# VCA.net
KiCad netlist of a schematic drawn in EAGLE
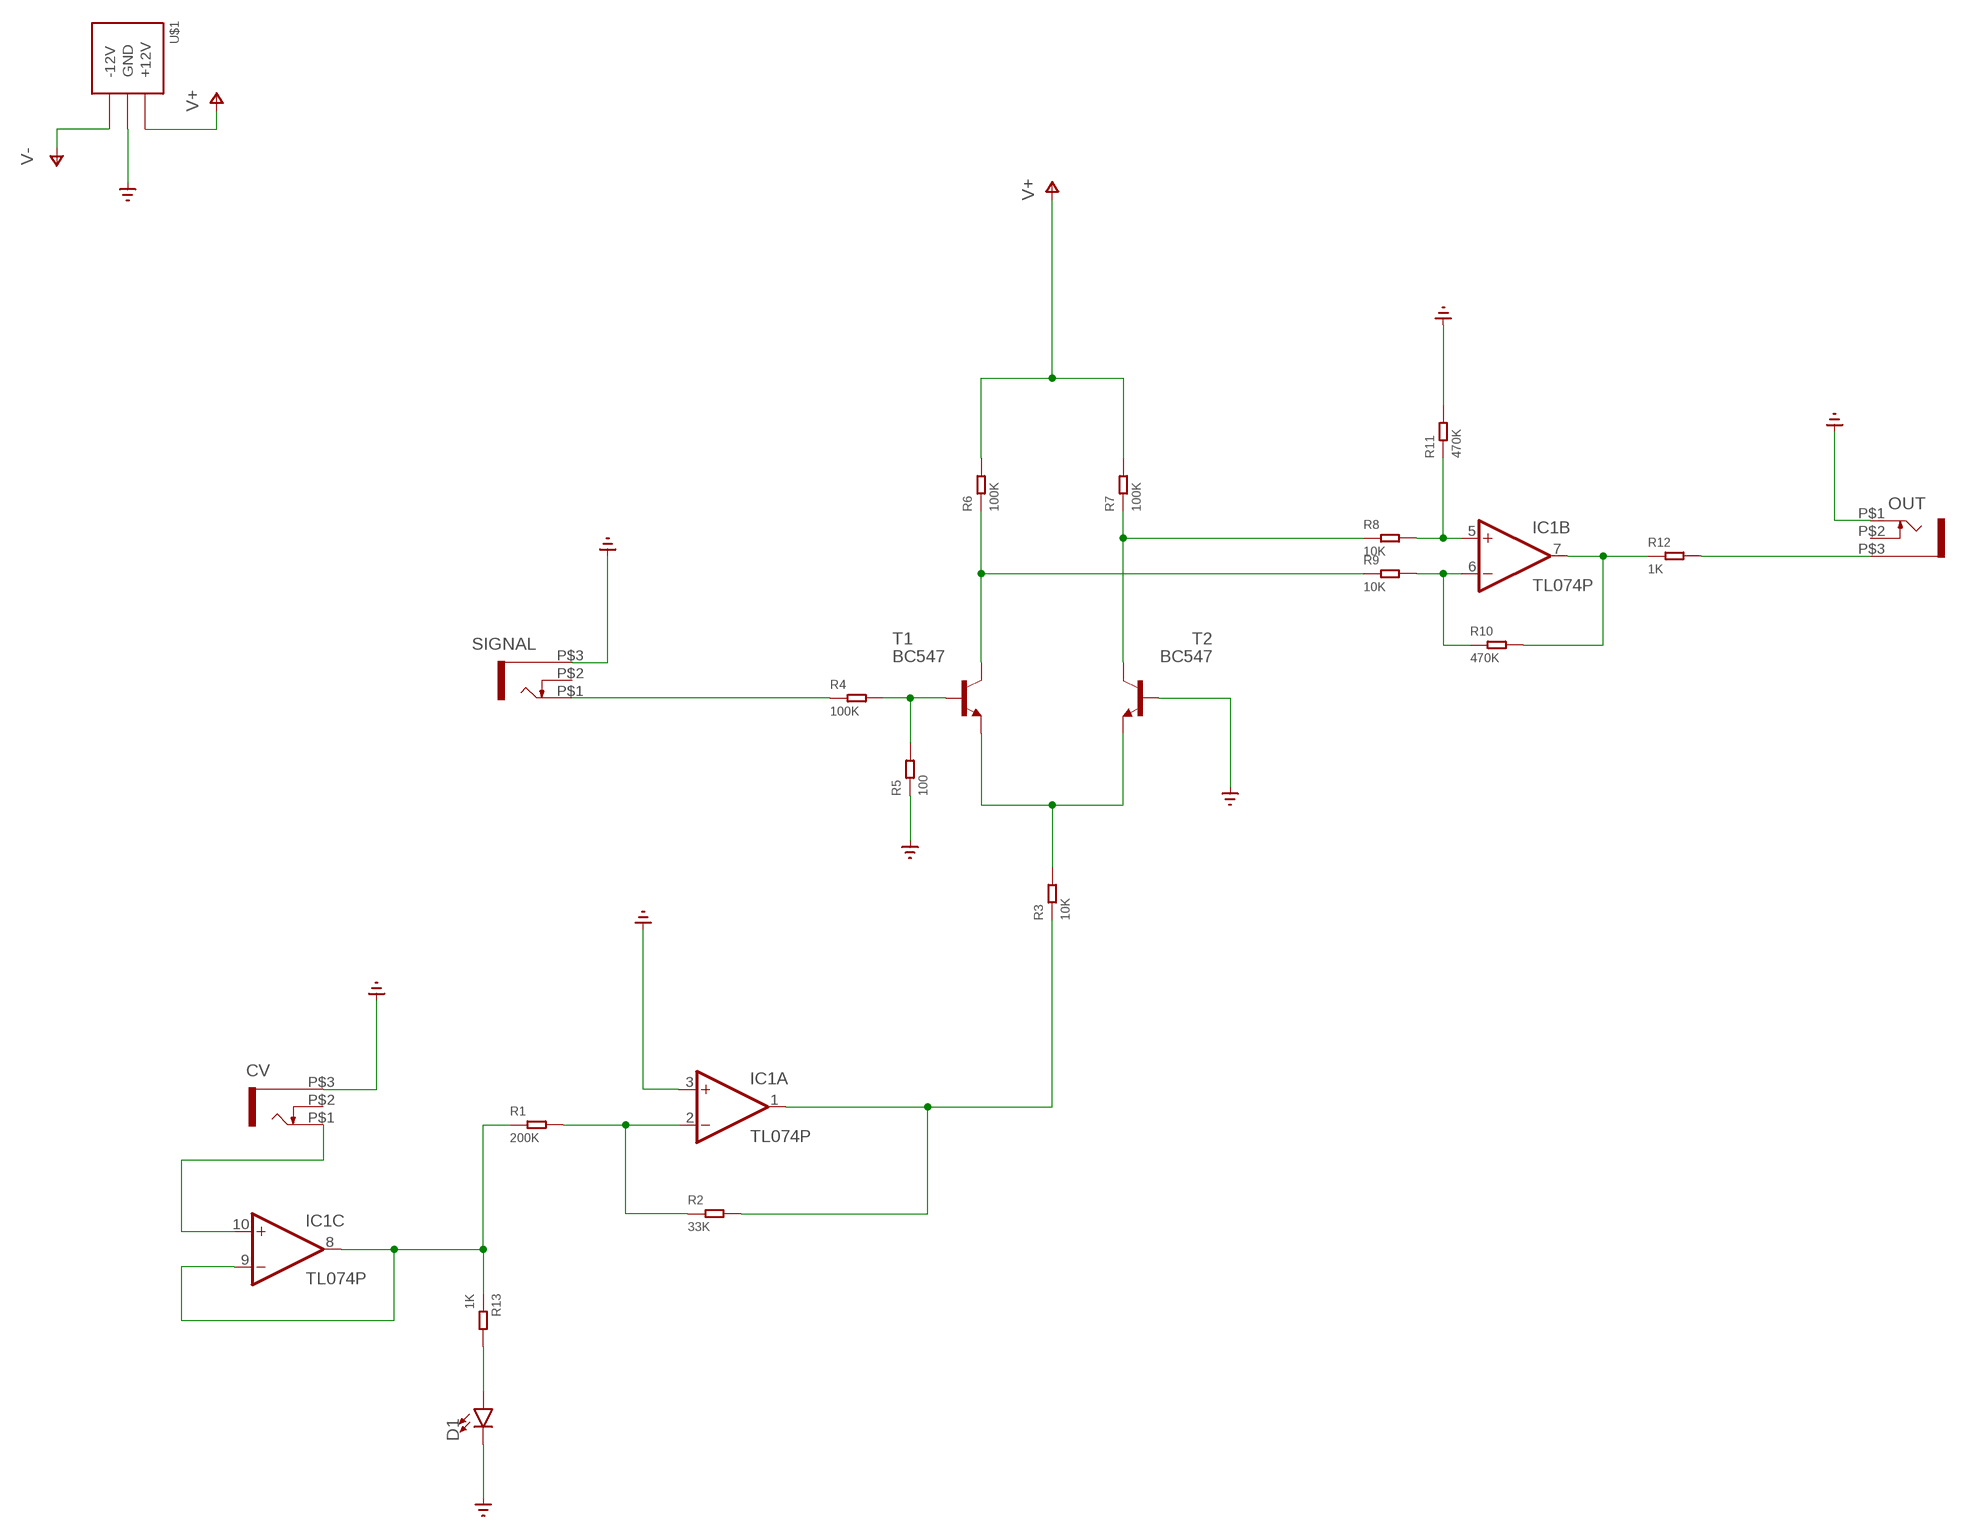
[diagram p0: schematic, sheet 1]

(export (version "E")
  (design (tool "Eeschema 10.0.6"))
  (components
    (comp (ref "CV")
      (value "WQP-PJ301M-12_JACK")
      (footprint "eagle-import:WQP-PJ301M-12_JACK")
      (libsource (lib "eagle-import") (part "WQP-PJ301M-12_JACK"))
    )
    (comp (ref "D1")
      (value "LED3MM")
      (footprint "eagle-import:LED_3MM")
      (libsource (lib "eagle-import") (part "LED3MM"))
    )
    (comp (ref "IC1")
      (value "TL074P")
      (footprint "eagle-import:DIL14")
      (libsource (lib "eagle-import") (part "TL074P"))
    )
    (comp (ref "OUT")
      (value "WQP-PJ301M-12_JACK")
      (footprint "eagle-import:WQP-PJ301M-12_JACK")
      (libsource (lib "eagle-import") (part "WQP-PJ301M-12_JACK"))
    )
    (comp (ref "R1")
      (value "200K")
      (footprint "eagle-import:PR-D2.3XL6.5MM")
      (fields (field (name "MPN") "FHCFR-1/4W-102J"))
      (libsource (lib "eagle-import") (part "DIP-RES-1K-5%-1/4W(PR-D2.3XL6.5MM)"))
    )
    (comp (ref "R2")
      (value "33K")
      (footprint "eagle-import:PR-D2.3XL6.5MM")
      (fields (field (name "MPN") "FHCFR-1/4W-102J"))
      (libsource (lib "eagle-import") (part "DIP-RES-1K-5%-1/4W(PR-D2.3XL6.5MM)"))
    )
    (comp (ref "R3")
      (value "10K")
      (footprint "eagle-import:PR-D2.3XL6.5MM")
      (fields (field (name "MPN") "FHCFR-1/4W-102J"))
      (libsource (lib "eagle-import") (part "DIP-RES-1K-5%-1/4W(PR-D2.3XL6.5MM)"))
    )
    (comp (ref "R4")
      (value "100K")
      (footprint "eagle-import:PR-D2.3XL6.5MM")
      (fields (field (name "MPN") "FHCFR-1/4W-102J"))
      (libsource (lib "eagle-import") (part "DIP-RES-1K-5%-1/4W(PR-D2.3XL6.5MM)"))
    )
    (comp (ref "R5")
      (value "100")
      (footprint "eagle-import:PR-D2.3XL6.5MM")
      (fields (field (name "MPN") "FHCFR-1/4W-102J"))
      (libsource (lib "eagle-import") (part "DIP-RES-1K-5%-1/4W(PR-D2.3XL6.5MM)"))
    )
    (comp (ref "R6")
      (value "100K")
      (footprint "eagle-import:PR-D2.3XL6.5MM")
      (fields (field (name "MPN") "FHCFR-1/4W-102J"))
      (libsource (lib "eagle-import") (part "DIP-RES-1K-5%-1/4W(PR-D2.3XL6.5MM)"))
    )
    (comp (ref "R7")
      (value "100K")
      (footprint "eagle-import:PR-D2.3XL6.5MM")
      (fields (field (name "MPN") "FHCFR-1/4W-102J"))
      (libsource (lib "eagle-import") (part "DIP-RES-1K-5%-1/4W(PR-D2.3XL6.5MM)"))
    )
    (comp (ref "R8")
      (value "10K")
      (footprint "eagle-import:PR-D2.3XL6.5MM")
      (fields (field (name "MPN") "FHCFR-1/4W-102J"))
      (libsource (lib "eagle-import") (part "DIP-RES-1K-5%-1/4W(PR-D2.3XL6.5MM)"))
    )
    (comp (ref "R9")
      (value "10K")
      (footprint "eagle-import:PR-D2.3XL6.5MM")
      (fields (field (name "MPN") "FHCFR-1/4W-102J"))
      (libsource (lib "eagle-import") (part "DIP-RES-1K-5%-1/4W(PR-D2.3XL6.5MM)"))
    )
    (comp (ref "R10")
      (value "470K")
      (footprint "eagle-import:PR-D2.3XL6.5MM")
      (fields (field (name "MPN") "FHCFR-1/4W-102J"))
      (libsource (lib "eagle-import") (part "DIP-RES-1K-5%-1/4W(PR-D2.3XL6.5MM)"))
    )
    (comp (ref "R11")
      (value "470K")
      (footprint "eagle-import:PR-D2.3XL6.5MM")
      (fields (field (name "MPN") "FHCFR-1/4W-102J"))
      (libsource (lib "eagle-import") (part "DIP-RES-1K-5%-1/4W(PR-D2.3XL6.5MM)"))
    )
    (comp (ref "R12")
      (value "1K")
      (footprint "eagle-import:PR-D2.3XL6.5MM")
      (fields (field (name "MPN") "FHCFR-1/4W-102J"))
      (libsource (lib "eagle-import") (part "DIP-RES-1K-5%-1/4W(PR-D2.3XL6.5MM)"))
    )
    (comp (ref "R13")
      (value "1K")
      (footprint "eagle-import:PR-D2.3XL6.5MM")
      (fields (field (name "MPN") "FHCFR-1/4W-102J"))
      (libsource (lib "eagle-import") (part "DIP-RES-1K-5%-1/4W(PR-D2.3XL6.5MM)"))
    )
    (comp (ref "SIGNAL")
      (value "WQP-PJ301M-12_JACK")
      (footprint "eagle-import:WQP-PJ301M-12_JACK")
      (libsource (lib "eagle-import") (part "WQP-PJ301M-12_JACK"))
    )
    (comp (ref "T1")
      (value "BC547")
      (footprint "eagle-import:TO92")
      (libsource (lib "eagle-import") (part "BC547"))
    )
    (comp (ref "T2")
      (value "BC547")
      (footprint "eagle-import:TO92")
      (libsource (lib "eagle-import") (part "BC547"))
    )
    (comp (ref "U$1")
      (value "POWER_SIMPLE10")
      (footprint "eagle-import:POWER_10")
      (libsource (lib "eagle-import") (part "POWER_SIMPLE10"))
    )
  )
  (nets
    (net (code "1") (name "Net-(CV-2)") (class "Default")
      (node (ref "CV") (pin "P$1") (pinfunction "2_P$1") (pintype "passive"))
      (node (ref "IC1") (pin "10") (pinfunction "+IN_10") (pintype "input"))
    )
    (net (code "2") (name "Net-(D1-PadA)") (class "Default")
      (node (ref "D1") (pin "A") (pinfunction "A_A") (pintype "passive"))
      (node (ref "R13") (pin "2") (pinfunction "2_2") (pintype "passive"))
    )
    (net (code "3") (name "Net-(IC1A--IN)") (class "Default")
      (node (ref "IC1") (pin "2") (pinfunction "-IN_2") (pintype "input"))
      (node (ref "R1") (pin "2") (pinfunction "2_2") (pintype "passive"))
      (node (ref "R2") (pin "1") (pinfunction "1_1") (pintype "passive"))
    )
    (net (code "4") (name "Net-(IC1A-OUT)") (class "Default")
      (node (ref "IC1") (pin "1") (pinfunction "OUT_1") (pintype "output"))
      (node (ref "R2") (pin "2") (pinfunction "2_2") (pintype "passive"))
      (node (ref "R3") (pin "1") (pinfunction "1_1") (pintype "passive"))
    )
    (net (code "5") (name "Net-(IC1B-+IN)") (class "Default")
      (node (ref "IC1") (pin "5") (pinfunction "+IN_5") (pintype "input"))
      (node (ref "R11") (pin "1") (pinfunction "1_1") (pintype "passive"))
      (node (ref "R8") (pin "2") (pinfunction "2_2") (pintype "passive"))
    )
    (net (code "6") (name "Net-(IC1B--IN)") (class "Default")
      (node (ref "IC1") (pin "6") (pinfunction "-IN_6") (pintype "input"))
      (node (ref "R10") (pin "1") (pinfunction "1_1") (pintype "passive"))
      (node (ref "R9") (pin "2") (pinfunction "2_2") (pintype "passive"))
    )
    (net (code "7") (name "Net-(IC1B-OUT)") (class "Default")
      (node (ref "IC1") (pin "7") (pinfunction "OUT_7") (pintype "output"))
      (node (ref "R10") (pin "2") (pinfunction "2_2") (pintype "passive"))
      (node (ref "R12") (pin "1") (pinfunction "1_1") (pintype "passive"))
    )
    (net (code "8") (name "Net-(IC1C--IN)") (class "Default")
      (node (ref "IC1") (pin "8") (pinfunction "OUT_8") (pintype "output"))
      (node (ref "IC1") (pin "9") (pinfunction "-IN_9") (pintype "input"))
      (node (ref "R1") (pin "1") (pinfunction "1_1") (pintype "passive"))
      (node (ref "R13") (pin "1") (pinfunction "1_1") (pintype "passive"))
    )
    (net (code "9") (name "Net-(OUT-1)") (class "Default")
      (node (ref "OUT") (pin "P$3") (pinfunction "1_P$3") (pintype "passive"))
      (node (ref "R12") (pin "2") (pinfunction "2_2") (pintype "passive"))
    )
    (net (code "10") (name "Net-(SIGNAL-2)") (class "Default")
      (node (ref "R4") (pin "1") (pinfunction "1_1") (pintype "passive"))
      (node (ref "SIGNAL") (pin "P$1") (pinfunction "2_P$1") (pintype "passive"))
    )
    (net (code "11") (name "Net-(T1-B)") (class "Default")
      (node (ref "R4") (pin "2") (pinfunction "2_2") (pintype "passive"))
      (node (ref "R5") (pin "2") (pinfunction "2_2") (pintype "passive"))
      (node (ref "T1") (pin "2") (pinfunction "B_2") (pintype "passive"))
    )
    (net (code "12") (name "Net-(T1-C)") (class "Default")
      (node (ref "R6") (pin "1") (pinfunction "1_1") (pintype "passive"))
      (node (ref "R9") (pin "1") (pinfunction "1_1") (pintype "passive"))
      (node (ref "T1") (pin "3") (pinfunction "C_3") (pintype "passive"))
    )
    (net (code "13") (name "Net-(T1-E)") (class "Default")
      (node (ref "R3") (pin "2") (pinfunction "2_2") (pintype "passive"))
      (node (ref "T1") (pin "1") (pinfunction "E_1") (pintype "passive"))
      (node (ref "T2") (pin "1") (pinfunction "E_1") (pintype "passive"))
    )
    (net (code "14") (name "Net-(T2-C)") (class "Default")
      (node (ref "R7") (pin "1") (pinfunction "1_1") (pintype "passive"))
      (node (ref "R8") (pin "1") (pinfunction "1_1") (pintype "passive"))
      (node (ref "T2") (pin "3") (pinfunction "C_3") (pintype "passive"))
    )
    (net (code "15") (name "SUPPLY0_GND_") (class "Default")
      (node (ref "CV") (pin "P$3") (pinfunction "1_P$3") (pintype "passive"))
      (node (ref "D1") (pin "K") (pinfunction "C_K") (pintype "passive"))
      (node (ref "IC1") (pin "3") (pinfunction "+IN_3") (pintype "input"))
      (node (ref "OUT") (pin "P$1") (pinfunction "2_P$1") (pintype "passive"))
      (node (ref "R11") (pin "2") (pinfunction "2_2") (pintype "passive"))
      (node (ref "R5") (pin "1") (pinfunction "1_1") (pintype "passive"))
      (node (ref "SIGNAL") (pin "P$3") (pinfunction "1_P$3") (pintype "passive"))
      (node (ref "T2") (pin "2") (pinfunction "B_2") (pintype "passive"))
      (node (ref "U$1") (pin "3") (pinfunction "GND_3") (pintype "bidirectional"))
      (node (ref "U$1") (pin "4") (pinfunction "GND_4") (pintype "bidirectional"))
      (node (ref "U$1") (pin "5") (pinfunction "GND_5") (pintype "bidirectional"))
      (node (ref "U$1") (pin "6") (pinfunction "GND_6") (pintype "bidirectional"))
      (node (ref "U$1") (pin "7") (pinfunction "GND_7") (pintype "bidirectional"))
      (node (ref "U$1") (pin "8") (pinfunction "GND_8") (pintype "bidirectional"))
    )
    (net (code "16") (name "V+") (class "Default")
      (node (ref "R6") (pin "2") (pinfunction "2_2") (pintype "passive"))
      (node (ref "R7") (pin "2") (pinfunction "2_2") (pintype "passive"))
      (node (ref "U$1") (pin "10") (pinfunction "+12V_10") (pintype "bidirectional"))
      (node (ref "U$1") (pin "9") (pinfunction "+12V_9") (pintype "bidirectional"))
    )
    (net (code "17") (name "V-") (class "Default")
      (node (ref "U$1") (pin "1") (pinfunction "-12V_1") (pintype "bidirectional"))
      (node (ref "U$1") (pin "2") (pinfunction "-12V_2") (pintype "bidirectional"))
    )
    (net (code "18") (name "unconnected-(CV-3-PadP$2)") (class "Default")
      (node (ref "CV") (pin "P$2") (pinfunction "3_P$2") (pintype "passive"))
    )
    (net (code "19") (name "unconnected-(OUT-3-PadP$2)") (class "Default")
      (node (ref "OUT") (pin "P$2") (pinfunction "3_P$2") (pintype "passive"))
    )
    (net (code "20") (name "unconnected-(SIGNAL-3-PadP$2)") (class "Default")
      (node (ref "SIGNAL") (pin "P$2") (pinfunction "3_P$2") (pintype "passive"))
    )
  )
)
